# receiver_ra02_5v.net
KiCad netlist of a schematic drawn in EAGLE
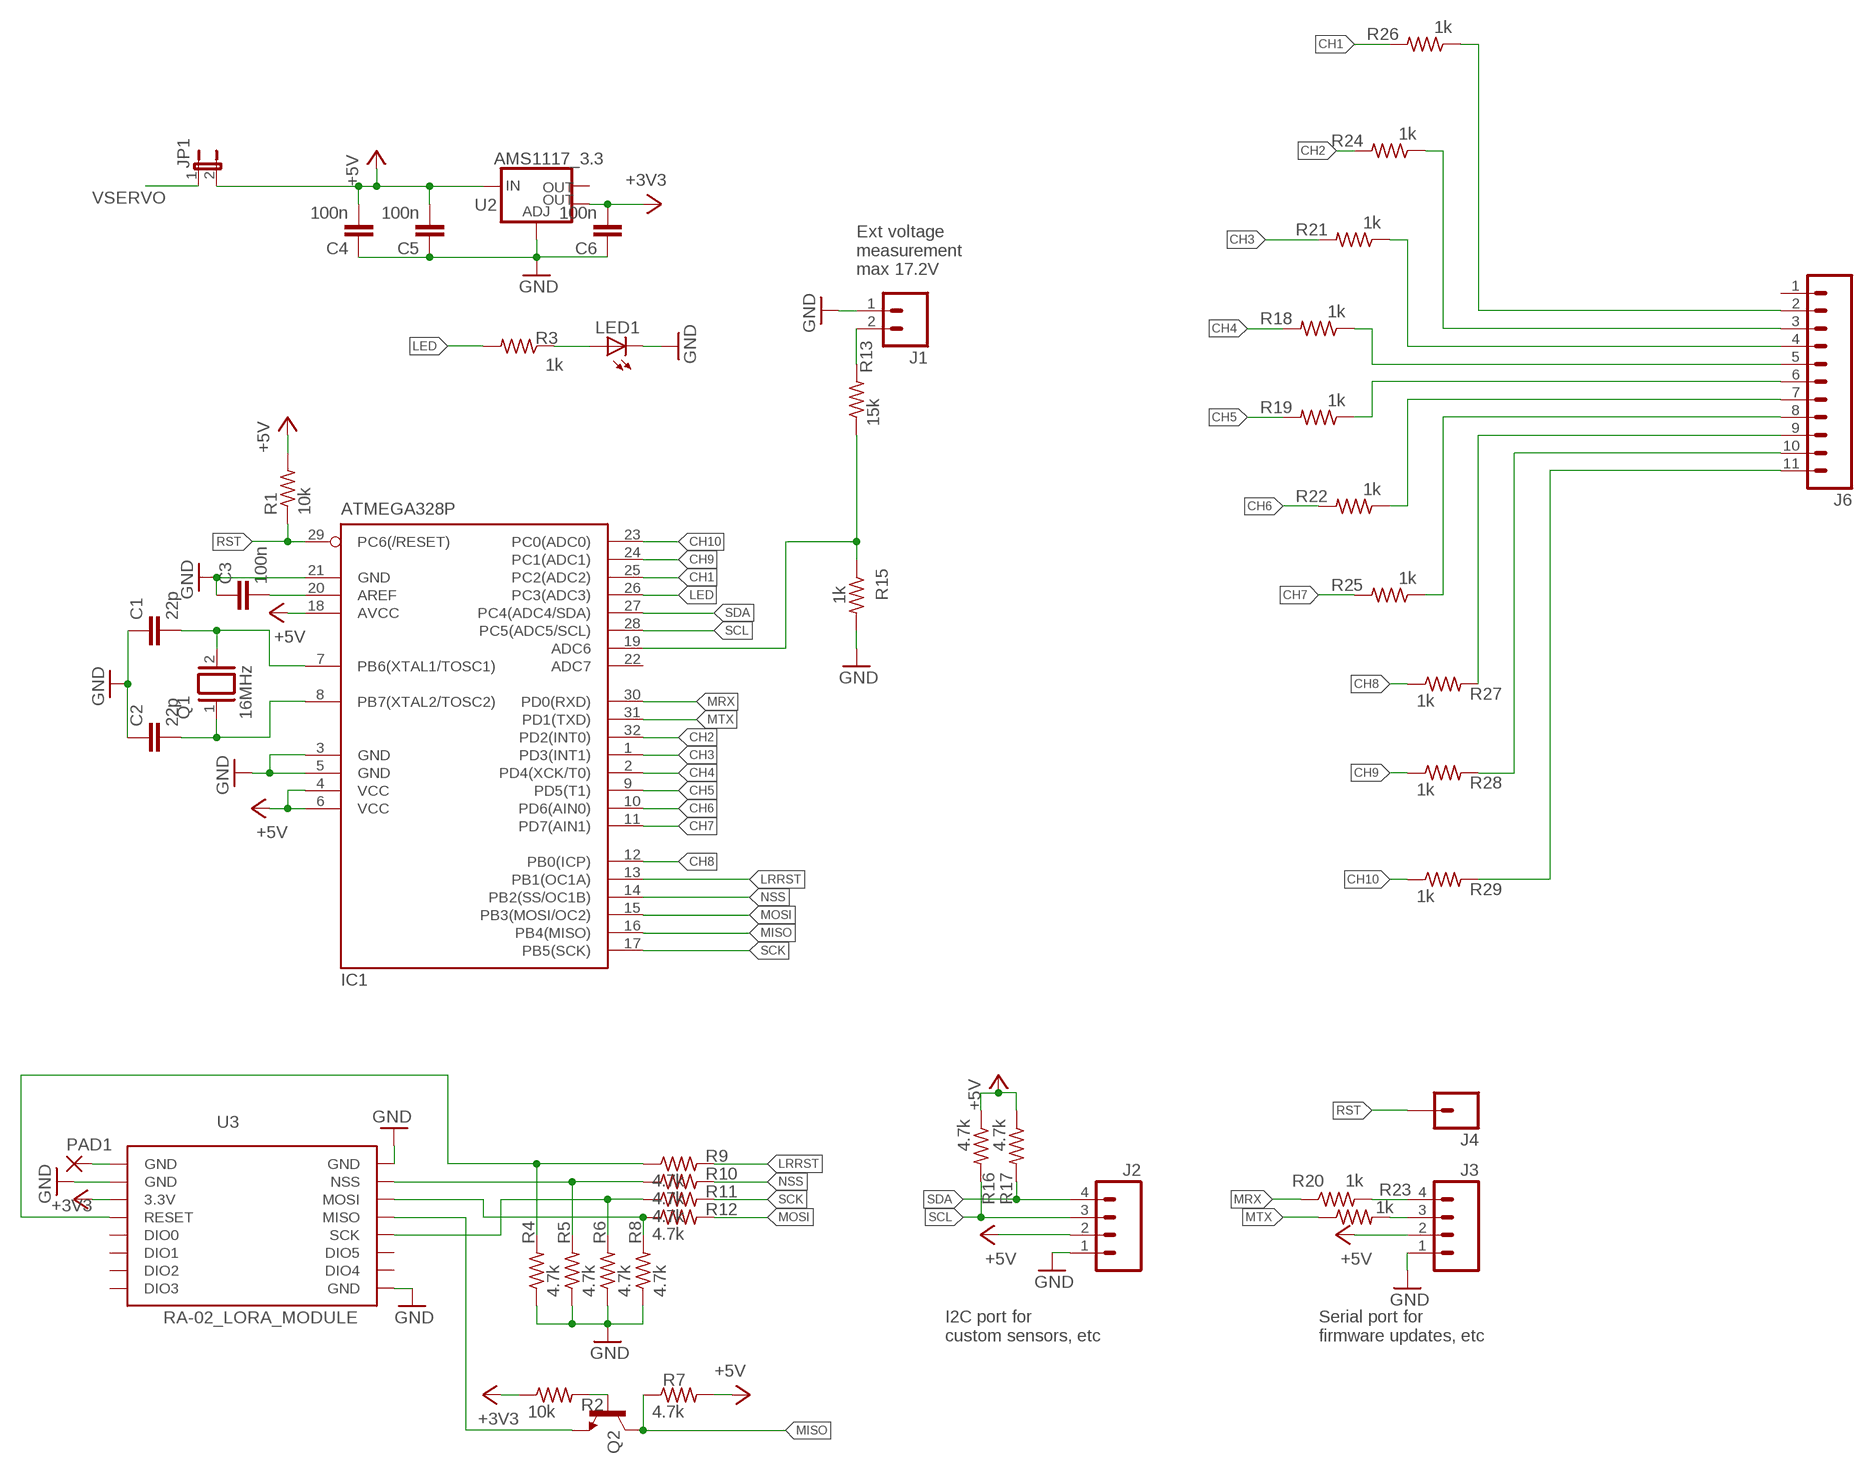
[diagram p0: schematic, sheet 1]

(export (version "E")
  (design (tool "Eeschema 10.0.6"))
  (components
    (comp (ref "C1")
      (value "22p")
      (footprint "eagle-import:C0805K")
      (libsource (lib "eagle-import") (part "C-EUC0805K"))
    )
    (comp (ref "C2")
      (value "22p")
      (footprint "eagle-import:C0805K")
      (libsource (lib "eagle-import") (part "C-EUC0805K"))
    )
    (comp (ref "C3")
      (value "100n")
      (footprint "eagle-import:C0805K")
      (libsource (lib "eagle-import") (part "C-EUC0805K"))
    )
    (comp (ref "C4")
      (value "100n")
      (footprint "eagle-import:C0805K")
      (libsource (lib "eagle-import") (part "C-EUC0805K"))
    )
    (comp (ref "C5")
      (value "100n")
      (footprint "eagle-import:C0805K")
      (libsource (lib "eagle-import") (part "C-EUC0805K"))
    )
    (comp (ref "C6")
      (value "100n")
      (footprint "eagle-import:C0805K")
      (libsource (lib "eagle-import") (part "C-EUC0805K"))
    )
    (comp (ref "IC1")
      (value "ATMEGA328P")
      (footprint "eagle-import:TQFP32-08")
      (fields (field (name "MPN") "ATMEGA8-16AU"))
      (libsource (lib "eagle-import") (part "MEGA8-AI"))
    )
    (comp (ref "J1")
      (value "M02PTH")
      (footprint "eagle-import:1X02")
      (libsource (lib "eagle-import") (part "M02PTH"))
    )
    (comp (ref "J2")
      (value "M04PTH")
      (footprint "eagle-import:1X04")
      (libsource (lib "eagle-import") (part "M04PTH"))
    )
    (comp (ref "J3")
      (value "M04PTH")
      (footprint "eagle-import:1X04")
      (libsource (lib "eagle-import") (part "M04PTH"))
    )
    (comp (ref "J4")
      (value "M01PTH")
      (footprint "eagle-import:1X01")
      (libsource (lib "eagle-import") (part "M01PTH"))
    )
    (comp (ref "J6")
      (value "M11PTH")
      (footprint "eagle-import:1X11")
      (libsource (lib "eagle-import") (part "M11PTH"))
    )
    (comp (ref "JP1")
      (value "JP1E")
      (footprint "eagle-import:JP1")
      (libsource (lib "eagle-import") (part "JP1E"))
    )
    (comp (ref "LED1")
      (value "LEDCHIPLED_1206")
      (footprint "eagle-import:CHIPLED_1206")
      (libsource (lib "eagle-import") (part "LEDCHIPLED_1206"))
    )
    (comp (ref "PAD1")
      (value "2,15/1,0")
      (footprint "eagle-import:2,15_1,0")
      (libsource (lib "eagle-import") (part "2,15/1,0"))
    )
    (comp (ref "Q1")
      (value "16MHz")
      (footprint "eagle-import:QS")
      (libsource (lib "eagle-import") (part "XTAL/S"))
    )
    (comp (ref "Q2")
      (value "BC817-16SMD")
      (footprint "eagle-import:SOT23-BEC")
      (libsource (lib "eagle-import") (part "BC817SMD-16"))
    )
    (comp (ref "R1")
      (value "10k")
      (footprint "eagle-import:R0805")
      (libsource (lib "eagle-import") (part "R-US_R0805"))
    )
    (comp (ref "R2")
      (value "10k")
      (footprint "eagle-import:R0805")
      (libsource (lib "eagle-import") (part "R-US_R0805"))
    )
    (comp (ref "R3")
      (value "1k")
      (footprint "eagle-import:R0805")
      (libsource (lib "eagle-import") (part "R-US_R0805"))
    )
    (comp (ref "R4")
      (value "4.7k")
      (footprint "eagle-import:R0805")
      (libsource (lib "eagle-import") (part "R-US_R0805"))
    )
    (comp (ref "R5")
      (value "4.7k")
      (footprint "eagle-import:R0805")
      (libsource (lib "eagle-import") (part "R-US_R0805"))
    )
    (comp (ref "R6")
      (value "4.7k")
      (footprint "eagle-import:R0805")
      (libsource (lib "eagle-import") (part "R-US_R0805"))
    )
    (comp (ref "R7")
      (value "4.7k")
      (footprint "eagle-import:R0805")
      (libsource (lib "eagle-import") (part "R-US_R0805"))
    )
    (comp (ref "R8")
      (value "4.7k")
      (footprint "eagle-import:R0805")
      (libsource (lib "eagle-import") (part "R-US_R0805"))
    )
    (comp (ref "R9")
      (value "4.7k")
      (footprint "eagle-import:R0805")
      (libsource (lib "eagle-import") (part "R-US_R0805"))
    )
    (comp (ref "R10")
      (value "4.7k")
      (footprint "eagle-import:R0805")
      (libsource (lib "eagle-import") (part "R-US_R0805"))
    )
    (comp (ref "R11")
      (value "4.7k")
      (footprint "eagle-import:R0805")
      (libsource (lib "eagle-import") (part "R-US_R0805"))
    )
    (comp (ref "R12")
      (value "4.7k")
      (footprint "eagle-import:R0805")
      (libsource (lib "eagle-import") (part "R-US_R0805"))
    )
    (comp (ref "R13")
      (value "15k")
      (footprint "eagle-import:R0805")
      (libsource (lib "eagle-import") (part "R-US_R0805"))
    )
    (comp (ref "R15")
      (value "1k")
      (footprint "eagle-import:R0805")
      (libsource (lib "eagle-import") (part "R-US_R0805"))
    )
    (comp (ref "R16")
      (value "4.7k")
      (footprint "eagle-import:R0805")
      (libsource (lib "eagle-import") (part "R-US_R0805"))
    )
    (comp (ref "R17")
      (value "4.7k")
      (footprint "eagle-import:R0805")
      (libsource (lib "eagle-import") (part "R-US_R0805"))
    )
    (comp (ref "R18")
      (value "1k")
      (footprint "eagle-import:R0805")
      (libsource (lib "eagle-import") (part "R-US_R0805"))
    )
    (comp (ref "R19")
      (value "1k")
      (footprint "eagle-import:R0805")
      (libsource (lib "eagle-import") (part "R-US_R0805"))
    )
    (comp (ref "R20")
      (value "1k")
      (footprint "eagle-import:R0805")
      (libsource (lib "eagle-import") (part "R-US_R0805"))
    )
    (comp (ref "R21")
      (value "1k")
      (footprint "eagle-import:R0805")
      (libsource (lib "eagle-import") (part "R-US_R0805"))
    )
    (comp (ref "R22")
      (value "1k")
      (footprint "eagle-import:R0805")
      (libsource (lib "eagle-import") (part "R-US_R0805"))
    )
    (comp (ref "R23")
      (value "1k")
      (footprint "eagle-import:R0805")
      (libsource (lib "eagle-import") (part "R-US_R0805"))
    )
    (comp (ref "R24")
      (value "1k")
      (footprint "eagle-import:R0805")
      (libsource (lib "eagle-import") (part "R-US_R0805"))
    )
    (comp (ref "R25")
      (value "1k")
      (footprint "eagle-import:R0805")
      (libsource (lib "eagle-import") (part "R-US_R0805"))
    )
    (comp (ref "R26")
      (value "1k")
      (footprint "eagle-import:R0805")
      (libsource (lib "eagle-import") (part "R-US_R0805"))
    )
    (comp (ref "R27")
      (value "1k")
      (footprint "eagle-import:R0805")
      (libsource (lib "eagle-import") (part "R-US_R0805"))
    )
    (comp (ref "R28")
      (value "1k")
      (footprint "eagle-import:R0805")
      (libsource (lib "eagle-import") (part "R-US_R0805"))
    )
    (comp (ref "R29")
      (value "1k")
      (footprint "eagle-import:R0805")
      (libsource (lib "eagle-import") (part "R-US_R0805"))
    )
    (comp (ref "U2")
      (value "AMS1117_3.3")
      (footprint "eagle-import:SOT223")
      (libsource (lib "eagle-import") (part "V_REG_LM1117SOT223"))
    )
    (comp (ref "U3")
      (value "RA-02_LORA_MODULE")
      (footprint "eagle-import:RA-02")
      (libsource (lib "eagle-import") (part "RA-02_LORA_MODULE"))
    )
  )
  (nets
    (net (code "1") (name "+3V3") (class "Default")
      (node (ref "C6") (pin "2") (pinfunction "2_2") (pintype "passive"))
      (node (ref "R2") (pin "1") (pinfunction "1_1") (pintype "passive"))
      (node (ref "U2") (pin "4") (pinfunction "OUT_4") (pintype "output"))
      (node (ref "U3") (pin "3.3V") (pinfunction "3.3V_3.3V") (pintype "power_in"))
    )
    (net (code "2") (name "+5V") (class "Default")
      (node (ref "C4") (pin "2") (pinfunction "2_2") (pintype "passive"))
      (node (ref "C5") (pin "2") (pinfunction "2_2") (pintype "passive"))
      (node (ref "IC1") (pin "18") (pinfunction "AVCC_18") (pintype "power_in"))
      (node (ref "IC1") (pin "4") (pinfunction "VCC_4") (pintype "power_in"))
      (node (ref "IC1") (pin "6") (pinfunction "VCC_6") (pintype "power_in"))
      (node (ref "J2") (pin "2") (pinfunction "2_2") (pintype "passive"))
      (node (ref "J3") (pin "2") (pinfunction "2_2") (pintype "passive"))
      (node (ref "JP1") (pin "2") (pinfunction "2_2") (pintype "passive"))
      (node (ref "R1") (pin "2") (pinfunction "2_2") (pintype "passive"))
      (node (ref "R16") (pin "1") (pinfunction "1_1") (pintype "passive"))
      (node (ref "R17") (pin "1") (pinfunction "1_1") (pintype "passive"))
      (node (ref "R7") (pin "2") (pinfunction "2_2") (pintype "passive"))
      (node (ref "U2") (pin "3") (pinfunction "IN_3") (pintype "input"))
    )
    (net (code "3") (name "/VSERVO") (class "Default")
      (node (ref "JP1") (pin "1") (pinfunction "1_1") (pintype "passive"))
    )
    (net (code "4") (name "CH1") (class "Default")
      (node (ref "IC1") (pin "25") (pinfunction "PC2(ADC2)_25") (pintype "bidirectional"))
      (node (ref "R26") (pin "2") (pinfunction "2_2") (pintype "passive"))
    )
    (net (code "5") (name "CH2") (class "Default")
      (node (ref "IC1") (pin "32") (pinfunction "PD2(INT0)_32") (pintype "bidirectional"))
      (node (ref "R24") (pin "2") (pinfunction "2_2") (pintype "passive"))
    )
    (net (code "6") (name "CH3") (class "Default")
      (node (ref "IC1") (pin "1") (pinfunction "PD3(INT1)_1") (pintype "bidirectional"))
      (node (ref "R21") (pin "2") (pinfunction "2_2") (pintype "passive"))
    )
    (net (code "7") (name "CH4") (class "Default")
      (node (ref "IC1") (pin "2") (pinfunction "PD4(XCK/T0)_2") (pintype "bidirectional"))
      (node (ref "R18") (pin "2") (pinfunction "2_2") (pintype "passive"))
    )
    (net (code "8") (name "CH5") (class "Default")
      (node (ref "IC1") (pin "9") (pinfunction "PD5(T1)_9") (pintype "bidirectional"))
      (node (ref "R19") (pin "2") (pinfunction "2_2") (pintype "passive"))
    )
    (net (code "9") (name "CH6") (class "Default")
      (node (ref "IC1") (pin "10") (pinfunction "PD6(AIN0)_10") (pintype "bidirectional"))
      (node (ref "R22") (pin "2") (pinfunction "2_2") (pintype "passive"))
    )
    (net (code "10") (name "CH7") (class "Default")
      (node (ref "IC1") (pin "11") (pinfunction "PD7(AIN1)_11") (pintype "bidirectional"))
      (node (ref "R25") (pin "2") (pinfunction "2_2") (pintype "passive"))
    )
    (net (code "11") (name "CH8") (class "Default")
      (node (ref "IC1") (pin "12") (pinfunction "PB0(ICP)_12") (pintype "bidirectional"))
      (node (ref "R27") (pin "1") (pinfunction "1_1") (pintype "passive"))
    )
    (net (code "12") (name "CH9") (class "Default")
      (node (ref "IC1") (pin "24") (pinfunction "PC1(ADC1)_24") (pintype "bidirectional"))
      (node (ref "R28") (pin "1") (pinfunction "1_1") (pintype "passive"))
    )
    (net (code "13") (name "CH10") (class "Default")
      (node (ref "IC1") (pin "23") (pinfunction "PC0(ADC0)_23") (pintype "bidirectional"))
      (node (ref "R29") (pin "1") (pinfunction "1_1") (pintype "passive"))
    )
    (net (code "14") (name "GND") (class "Default")
      (node (ref "C1") (pin "1") (pinfunction "1_1") (pintype "passive"))
      (node (ref "C2") (pin "1") (pinfunction "1_1") (pintype "passive"))
      (node (ref "C3") (pin "1") (pinfunction "1_1") (pintype "passive"))
      (node (ref "C4") (pin "1") (pinfunction "1_1") (pintype "passive"))
      (node (ref "C5") (pin "1") (pinfunction "1_1") (pintype "passive"))
      (node (ref "C6") (pin "1") (pinfunction "1_1") (pintype "passive"))
      (node (ref "IC1") (pin "21") (pinfunction "GND_21") (pintype "power_in"))
      (node (ref "IC1") (pin "3") (pinfunction "GND_3") (pintype "power_in"))
      (node (ref "IC1") (pin "5") (pinfunction "GND_5") (pintype "power_in"))
      (node (ref "J1") (pin "1") (pinfunction "1_1") (pintype "passive"))
      (node (ref "J2") (pin "1") (pinfunction "1_1") (pintype "passive"))
      (node (ref "J3") (pin "1") (pinfunction "1_1") (pintype "passive"))
      (node (ref "LED1") (pin "C") (pinfunction "C_C") (pintype "passive"))
      (node (ref "R15") (pin "2") (pinfunction "2_2") (pintype "passive"))
      (node (ref "R4") (pin "1") (pinfunction "1_1") (pintype "passive"))
      (node (ref "R5") (pin "1") (pinfunction "1_1") (pintype "passive"))
      (node (ref "R6") (pin "1") (pinfunction "1_1") (pintype "passive"))
      (node (ref "R8") (pin "1") (pinfunction "1_1") (pintype "passive"))
      (node (ref "U2") (pin "1") (pinfunction "ADJ_1") (pintype "input"))
      (node (ref "U3") (pin "GND@2") (pinfunction "GND_GND@2") (pintype "power_in"))
      (node (ref "U3") (pin "GND@3") (pinfunction "GND_GND@3") (pintype "power_in"))
      (node (ref "U3") (pin "GND@4") (pinfunction "GND_GND@4") (pintype "power_in"))
    )
    (net (code "15") (name "LED") (class "Default")
      (node (ref "IC1") (pin "26") (pinfunction "PC3(ADC3)_26") (pintype "bidirectional"))
      (node (ref "R3") (pin "2") (pinfunction "2_2") (pintype "passive"))
    )
    (net (code "16") (name "LRRST") (class "Default")
      (node (ref "IC1") (pin "13") (pinfunction "PB1(OC1A)_13") (pintype "bidirectional"))
      (node (ref "R9") (pin "2") (pinfunction "2_2") (pintype "passive"))
    )
    (net (code "17") (name "MISO") (class "Default")
      (node (ref "IC1") (pin "16") (pinfunction "PB4(MISO)_16") (pintype "bidirectional"))
      (node (ref "Q2") (pin "C") (pinfunction "C_C") (pintype "passive"))
      (node (ref "R7") (pin "1") (pinfunction "1_1") (pintype "passive"))
    )
    (net (code "18") (name "MOSI") (class "Default")
      (node (ref "IC1") (pin "15") (pinfunction "PB3(MOSI/OC2)_15") (pintype "bidirectional"))
      (node (ref "R12") (pin "2") (pinfunction "2_2") (pintype "passive"))
    )
    (net (code "19") (name "MRX") (class "Default")
      (node (ref "IC1") (pin "30") (pinfunction "PD0(RXD)_30") (pintype "bidirectional"))
      (node (ref "R20") (pin "1") (pinfunction "1_1") (pintype "passive"))
    )
    (net (code "20") (name "MTX") (class "Default")
      (node (ref "IC1") (pin "31") (pinfunction "PD1(TXD)_31") (pintype "bidirectional"))
      (node (ref "R23") (pin "1") (pinfunction "1_1") (pintype "passive"))
    )
    (net (code "21") (name "NSS") (class "Default")
      (node (ref "IC1") (pin "14") (pinfunction "PB2(SS/OC1B)_14") (pintype "bidirectional"))
      (node (ref "R10") (pin "2") (pinfunction "2_2") (pintype "passive"))
    )
    (net (code "22") (name "Net-(IC1-ADC6)") (class "Default")
      (node (ref "IC1") (pin "19") (pinfunction "ADC6_19") (pintype "bidirectional"))
      (node (ref "R13") (pin "1") (pinfunction "1_1") (pintype "passive"))
      (node (ref "R15") (pin "1") (pinfunction "1_1") (pintype "passive"))
    )
    (net (code "23") (name "Net-(IC1-AREF)") (class "Default")
      (node (ref "C3") (pin "2") (pinfunction "2_2") (pintype "passive"))
      (node (ref "IC1") (pin "20") (pinfunction "AREF_20") (pintype "passive"))
    )
    (net (code "24") (name "Net-(IC1-PB6(XTAL1{slash}TOSC1))") (class "Default")
      (node (ref "C1") (pin "2") (pinfunction "2_2") (pintype "passive"))
      (node (ref "IC1") (pin "7") (pinfunction "PB6(XTAL1/TOSC1)_7") (pintype "bidirectional"))
      (node (ref "Q1") (pin "2") (pinfunction "2_2") (pintype "passive"))
    )
    (net (code "25") (name "Net-(IC1-PB7(XTAL2{slash}TOSC2))") (class "Default")
      (node (ref "C2") (pin "2") (pinfunction "2_2") (pintype "passive"))
      (node (ref "IC1") (pin "8") (pinfunction "PB7(XTAL2/TOSC2)_8") (pintype "bidirectional"))
      (node (ref "Q1") (pin "1") (pinfunction "1_1") (pintype "passive"))
    )
    (net (code "26") (name "Net-(J1-Pad2)") (class "Default")
      (node (ref "J1") (pin "2") (pinfunction "2_2") (pintype "passive"))
      (node (ref "R13") (pin "2") (pinfunction "2_2") (pintype "passive"))
    )
    (net (code "27") (name "Net-(J3-Pad3)") (class "Default")
      (node (ref "J3") (pin "3") (pinfunction "3_3") (pintype "passive"))
      (node (ref "R23") (pin "2") (pinfunction "2_2") (pintype "passive"))
    )
    (net (code "28") (name "Net-(J3-Pad4)") (class "Default")
      (node (ref "J3") (pin "4") (pinfunction "4_4") (pintype "passive"))
      (node (ref "R20") (pin "2") (pinfunction "2_2") (pintype "passive"))
    )
    (net (code "29") (name "Net-(J6-Pad2)") (class "Default")
      (node (ref "J6") (pin "2") (pinfunction "2_2") (pintype "passive"))
      (node (ref "R26") (pin "1") (pinfunction "1_1") (pintype "passive"))
    )
    (net (code "30") (name "Net-(J6-Pad3)") (class "Default")
      (node (ref "J6") (pin "3") (pinfunction "3_3") (pintype "passive"))
      (node (ref "R24") (pin "1") (pinfunction "1_1") (pintype "passive"))
    )
    (net (code "31") (name "Net-(J6-Pad4)") (class "Default")
      (node (ref "J6") (pin "4") (pinfunction "4_4") (pintype "passive"))
      (node (ref "R21") (pin "1") (pinfunction "1_1") (pintype "passive"))
    )
    (net (code "32") (name "Net-(J6-Pad5)") (class "Default")
      (node (ref "J6") (pin "5") (pinfunction "5_5") (pintype "passive"))
      (node (ref "R18") (pin "1") (pinfunction "1_1") (pintype "passive"))
    )
    (net (code "33") (name "Net-(J6-Pad6)") (class "Default")
      (node (ref "J6") (pin "6") (pinfunction "6_6") (pintype "passive"))
      (node (ref "R19") (pin "1") (pinfunction "1_1") (pintype "passive"))
    )
    (net (code "34") (name "Net-(J6-Pad7)") (class "Default")
      (node (ref "J6") (pin "7") (pinfunction "7_7") (pintype "passive"))
      (node (ref "R22") (pin "1") (pinfunction "1_1") (pintype "passive"))
    )
    (net (code "35") (name "Net-(J6-Pad8)") (class "Default")
      (node (ref "J6") (pin "8") (pinfunction "8_8") (pintype "passive"))
      (node (ref "R25") (pin "1") (pinfunction "1_1") (pintype "passive"))
    )
    (net (code "36") (name "Net-(J6-Pad9)") (class "Default")
      (node (ref "J6") (pin "9") (pinfunction "9_9") (pintype "passive"))
      (node (ref "R27") (pin "2") (pinfunction "2_2") (pintype "passive"))
    )
    (net (code "37") (name "Net-(J6-Pad10)") (class "Default")
      (node (ref "J6") (pin "10") (pinfunction "10_10") (pintype "passive"))
      (node (ref "R28") (pin "2") (pinfunction "2_2") (pintype "passive"))
    )
    (net (code "38") (name "Net-(J6-Pad11)") (class "Default")
      (node (ref "J6") (pin "11") (pinfunction "11_11") (pintype "passive"))
      (node (ref "R29") (pin "2") (pinfunction "2_2") (pintype "passive"))
    )
    (net (code "39") (name "Net-(LED1-PadA)") (class "Default")
      (node (ref "LED1") (pin "A") (pinfunction "A_A") (pintype "passive"))
      (node (ref "R3") (pin "1") (pinfunction "1_1") (pintype "passive"))
    )
    (net (code "40") (name "Net-(PAD1-P)") (class "Default")
      (node (ref "PAD1") (pin "1") (pinfunction "P_1") (pintype "passive"))
      (node (ref "U3") (pin "GND") (pinfunction "GND_GND") (pintype "power_in"))
    )
    (net (code "41") (name "Net-(Q2-PadB)") (class "Default")
      (node (ref "Q2") (pin "B") (pinfunction "B_B") (pintype "passive"))
      (node (ref "R2") (pin "2") (pinfunction "2_2") (pintype "passive"))
    )
    (net (code "42") (name "Net-(Q2-PadE)") (class "Default")
      (node (ref "Q2") (pin "E") (pinfunction "E_E") (pintype "passive"))
      (node (ref "U3") (pin "MISO") (pinfunction "MISO_MISO") (pintype "bidirectional"))
    )
    (net (code "43") (name "Net-(R4-Pad2)") (class "Default")
      (node (ref "R4") (pin "2") (pinfunction "2_2") (pintype "passive"))
      (node (ref "R9") (pin "1") (pinfunction "1_1") (pintype "passive"))
      (node (ref "U3") (pin "RESET") (pinfunction "RESET_RESET") (pintype "bidirectional"))
    )
    (net (code "44") (name "Net-(R10-Pad1)") (class "Default")
      (node (ref "R10") (pin "1") (pinfunction "1_1") (pintype "passive"))
      (node (ref "R5") (pin "2") (pinfunction "2_2") (pintype "passive"))
      (node (ref "U3") (pin "NSS") (pinfunction "NSS_NSS") (pintype "bidirectional"))
    )
    (net (code "45") (name "Net-(R11-Pad1)") (class "Default")
      (node (ref "R11") (pin "1") (pinfunction "1_1") (pintype "passive"))
      (node (ref "R6") (pin "2") (pinfunction "2_2") (pintype "passive"))
      (node (ref "U3") (pin "SCK") (pinfunction "SCK_SCK") (pintype "bidirectional"))
    )
    (net (code "46") (name "Net-(R12-Pad1)") (class "Default")
      (node (ref "R12") (pin "1") (pinfunction "1_1") (pintype "passive"))
      (node (ref "R8") (pin "2") (pinfunction "2_2") (pintype "passive"))
      (node (ref "U3") (pin "MOSI") (pinfunction "MOSI_MOSI") (pintype "bidirectional"))
    )
    (net (code "47") (name "RST") (class "Default")
      (node (ref "IC1") (pin "29") (pinfunction "PC6(/RESET)_29") (pintype "bidirectional"))
      (node (ref "J4") (pin "1") (pinfunction "1_1") (pintype "passive"))
      (node (ref "R1") (pin "1") (pinfunction "1_1") (pintype "passive"))
    )
    (net (code "48") (name "SCK") (class "Default")
      (node (ref "IC1") (pin "17") (pinfunction "PB5(SCK)_17") (pintype "bidirectional"))
      (node (ref "R11") (pin "2") (pinfunction "2_2") (pintype "passive"))
    )
    (net (code "49") (name "SCL") (class "Default")
      (node (ref "IC1") (pin "28") (pinfunction "PC5(ADC5/SCL)_28") (pintype "bidirectional"))
      (node (ref "J2") (pin "3") (pinfunction "3_3") (pintype "passive"))
      (node (ref "R16") (pin "2") (pinfunction "2_2") (pintype "passive"))
    )
    (net (code "50") (name "SDA") (class "Default")
      (node (ref "IC1") (pin "27") (pinfunction "PC4(ADC4/SDA)_27") (pintype "bidirectional"))
      (node (ref "J2") (pin "4") (pinfunction "4_4") (pintype "passive"))
      (node (ref "R17") (pin "2") (pinfunction "2_2") (pintype "passive"))
    )
    (net (code "51") (name "unconnected-(IC1-ADC7-Pad22)") (class "Default")
      (node (ref "IC1") (pin "22") (pinfunction "ADC7_22") (pintype "bidirectional"))
    )
    (net (code "52") (name "unconnected-(J6-Pad1)") (class "Default")
      (node (ref "J6") (pin "1") (pinfunction "1_1") (pintype "passive"))
    )
    (net (code "53") (name "unconnected-(U2-OUT-Pad2)") (class "Default")
      (node (ref "U2") (pin "2") (pinfunction "OUT_2") (pintype "output"))
    )
    (net (code "54") (name "unconnected-(U3-PadDIO0)") (class "Default")
      (node (ref "U3") (pin "DIO0") (pinfunction "DIO0_DIO0") (pintype "bidirectional"))
    )
    (net (code "55") (name "unconnected-(U3-PadDIO1)") (class "Default")
      (node (ref "U3") (pin "DIO1") (pinfunction "DIO1_DIO1") (pintype "bidirectional"))
    )
    (net (code "56") (name "unconnected-(U3-PadDIO2)") (class "Default")
      (node (ref "U3") (pin "DIO2") (pinfunction "DIO2_DIO2") (pintype "bidirectional"))
    )
    (net (code "57") (name "unconnected-(U3-PadDIO3)") (class "Default")
      (node (ref "U3") (pin "DIO3") (pinfunction "DIO3_DIO3") (pintype "bidirectional"))
    )
    (net (code "58") (name "unconnected-(U3-PadDIO4)") (class "Default")
      (node (ref "U3") (pin "DIO4") (pinfunction "DIO4_DIO4") (pintype "bidirectional"))
    )
    (net (code "59") (name "unconnected-(U3-PadDIO5)") (class "Default")
      (node (ref "U3") (pin "DIO5") (pinfunction "DIO5_DIO5") (pintype "bidirectional"))
    )
  )
)
